# Sheet.net
KiCad netlist of a schematic drawn in Altium Designer
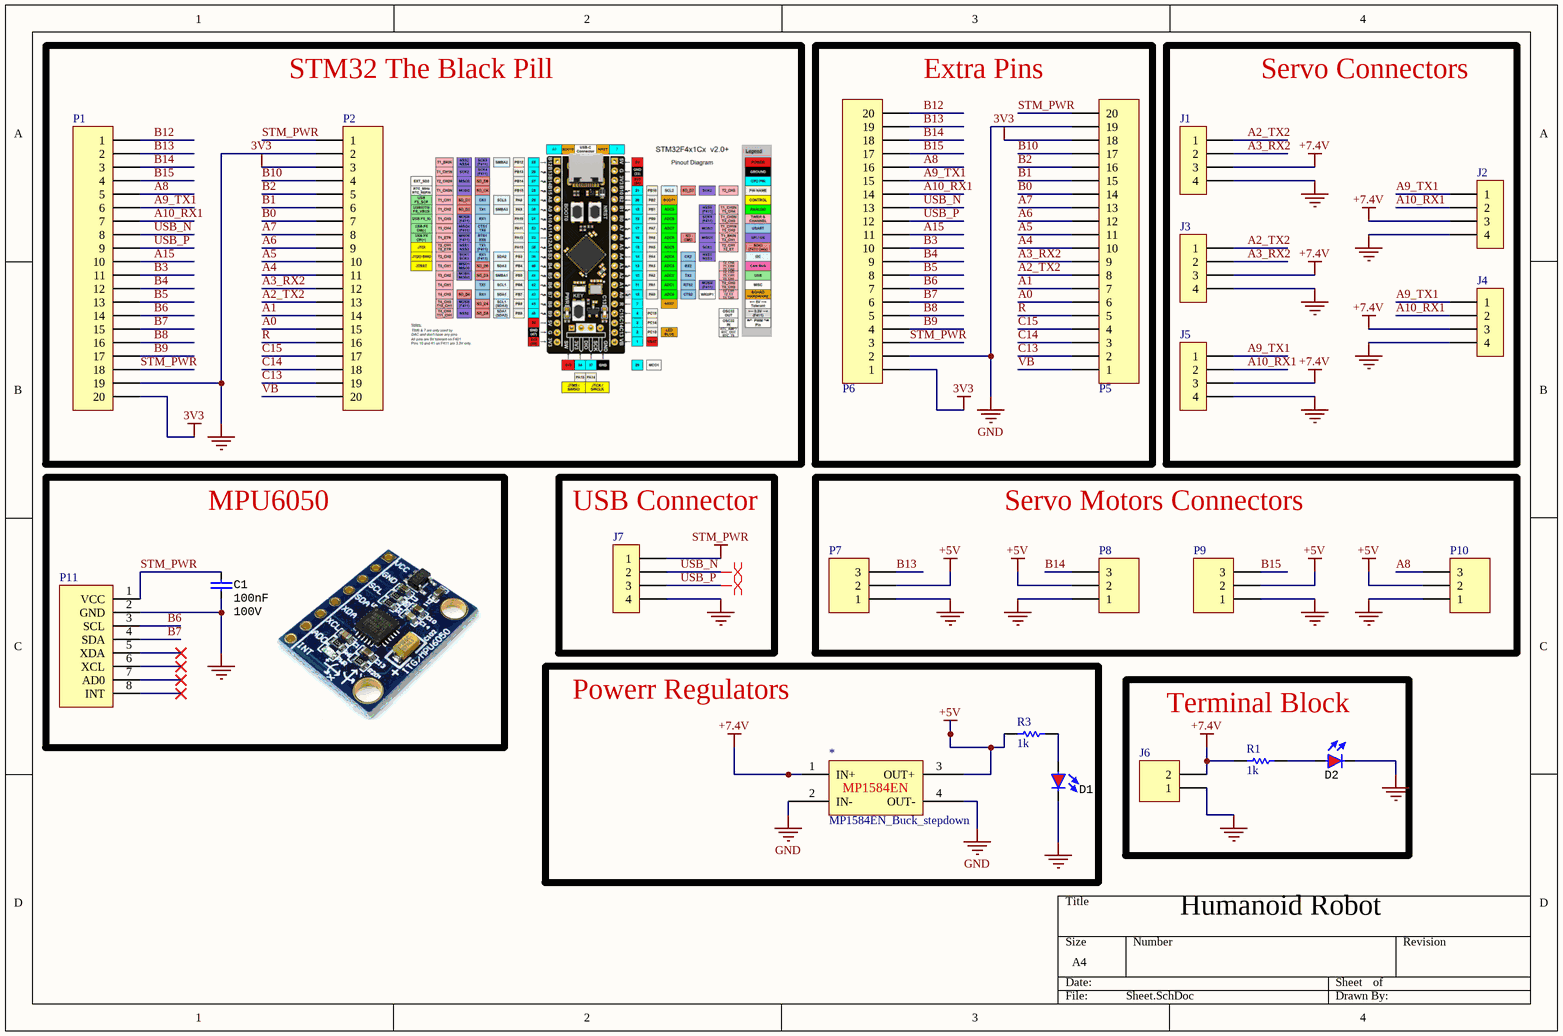
[diagram p0: Sheet.SchDoc]

(export (version "E")
  (design (tool "Eeschema 10.0.6"))
  (components
    (comp (ref "*")
      (value "MP1584EN_Buck_stepdown")
      (footprint "MP1584EN_MODULE")
      (libsource (lib "GradPcb_schlib") (part "MP1584EN_Buck_stepdown"))
    )
    (comp (ref "C1")
      (value "100nF")
      (footprint "CAP Ceramic SMD 0603")
      (description "100V 100nF X7R ±10% 0603 Multilayer Ceramic Capacitors MLCC - SMD/SMT ROHS")
      (fields
        (field (name "MANUFACTURER") "Yageo")
        (field (name "MANUFACTURER PART NUMBER") "CC0603KRX7R0BB104")
        (field (name "VOLTAGE") "100V")
      )
      (libsource (lib "Passive") (part "CAP 0603 100nF 100V X7R 10%"))
    )
    (comp (ref "D1")
      (value "~")
      (footprint "LED SMD 0805R")
      (description "red 0805 Light Emitting Diodes (LED) ROHS")
      (fields
        (field (name "MANUFACTURER") "FOSHAN Nationstar Optoelectronics")
        (field (name "MANUFACTURER PART NUMBER") "NCD0805R1")
      )
      (libsource (lib "diode") (part "LED 0805 Red"))
    )
    (comp (ref "D2")
      (value "~")
      (footprint "LED SMD 0805R")
      (description "red 0805 Light Emitting Diodes (LED) ROHS")
      (fields
        (field (name "MANUFACTURER") "FOSHAN Nationstar Optoelectronics")
        (field (name "MANUFACTURER PART NUMBER") "NCD0805R1")
      )
      (libsource (lib "diode") (part "LED 0805 Red"))
    )
    (comp (ref "J1")
      (value "JST 4")
      (footprint "XH4/2.54mm/180")
      (description "MaleHeader 4x1")
      (libsource (lib "Signal connectors") (part "JST 4"))
    )
    (comp (ref "J2")
      (value "JST 4")
      (footprint "XH4/2.54mm/180")
      (description "MaleHeader 4x1")
      (libsource (lib "") (part "JST 4_1"))
    )
    (comp (ref "J3")
      (value "JST 4")
      (footprint "XH4/2.54mm/180")
      (description "MaleHeader 4x1")
      (libsource (lib "Signal connectors") (part "JST 4"))
    )
    (comp (ref "J4")
      (value "JST 4")
      (footprint "XH4/2.54mm/180")
      (description "MaleHeader 4x1")
      (libsource (lib "") (part "JST 4_1"))
    )
    (comp (ref "J5")
      (value "JST 4")
      (footprint "XH4/2.54mm/180")
      (description "MaleHeader 4x1")
      (libsource (lib "Signal connectors") (part "JST 4"))
    )
    (comp (ref "J6")
      (value "PWR IN")
      (footprint "Connector screw terminal Block TH 1x2 5.0")
      (description "691214110002 - Wire-To-Board Terminal Block, 3.5 mm, 2 Positions, 24 AWG, 16 AWG, 1.5 mm², Screw")
      (fields
        (field (name "MANUFACTURER") "Wurth Electronics")
        (field (name "MANUFACTURER PART NUMBER") "691214110002")
      )
      (libsource (lib "Power connectors") (part "connector screw terminal 1x2"))
    )
    (comp (ref "J7")
      (value "JST 4")
      (footprint "XH4/2.54mm/180")
      (description "MaleHeader 4x1")
      (libsource (lib "Signal connectors") (part "JST 4"))
    )
    (comp (ref "P1")
      (value "Connector Pinheader 1x20")
      (footprint "Header F 2.54X20")
      (description "Header_20x1")
      (libsource (lib "Signal connectors") (part "Connector Pinheader 1x20"))
    )
    (comp (ref "P2")
      (value "Connector Pinheader 1x20")
      (footprint "Header F 2.54X20")
      (description "Header_20x1")
      (libsource (lib "") (part "Connector Pinheader 1x20_1"))
    )
    (comp (ref "P5")
      (value "Connector Pinheader 1x20")
      (footprint "Header F 2.54X20")
      (description "Header_20x1")
      (libsource (lib "") (part "Connector Pinheader 1x20_1"))
    )
    (comp (ref "P6")
      (value "Connector Pinheader 1x20")
      (footprint "Header F 2.54X20")
      (description "Header_20x1")
      (libsource (lib "GradPcb_schlib") (part "Connector Pinheader 1x20"))
    )
    (comp (ref "P7")
      (value "L_gripper")
      (footprint "Header 2.54X3")
      (description "Header_3x1")
      (libsource (lib "") (part "Connector Pinheader 1x3_1"))
    )
    (comp (ref "P8")
      (value "Connector Pinheader 1x3")
      (footprint "Header 2.54X3")
      (description "Header_3x1")
      (libsource (lib "Signal connectors") (part "Connector Pinheader 1x3"))
    )
    (comp (ref "P9")
      (value "R_gripper")
      (footprint "Header 2.54X3")
      (description "Header_3x1")
      (libsource (lib "") (part "Connector Pinheader 1x3_1"))
    )
    (comp (ref "P10")
      (value "Connector Pinheader 1x3")
      (footprint "Header 2.54X3")
      (description "Header_3x1")
      (libsource (lib "Signal connectors") (part "Connector Pinheader 1x3"))
    )
    (comp (ref "P11")
      (value "MPU6050 (GY-521 Module)")
      (footprint "MPU6050 (GY-521 Module)")
      (libsource (lib "Modules") (part "MPU6050 (GY-521 Module)"))
    )
    (comp (ref "R1")
      (value "1k")
      (footprint "RESC2013X70X40ML20T20")
      (description "Chip Resistor, 1 KOhm, +/- 1%, 0.125 W, -55 to 155 degC, 0805 (2013 Metric)")
      (fields (field (name "TOLERANCE") "1%") (field (name "POWER") "125mW"))
      (libsource (lib "Nour's Workspace") (part "RES-2"))
    )
    (comp (ref "R3")
      (value "1k")
      (footprint "RESC2013X70X40ML20T20")
      (description "Chip Resistor, 1 KOhm, +/- 1%, 0.125 W, -55 to 155 degC, 0805 (2013 Metric)")
      (fields (field (name "TOLERANCE") "1%") (field (name "POWER") "125mW"))
      (libsource (lib "Nour's Workspace") (part "RES-2"))
    )
  )
  (nets
    (net (code "1") (name "+5V") (class "Default")
      (node (ref "*") (pin "3") (pinfunction "OUT+_3") (pintype "passive"))
      (node (ref "P10") (pin "2") (pinfunction "2_2") (pintype "passive"))
      (node (ref "P7") (pin "2") (pinfunction "2_2") (pintype "passive"))
      (node (ref "P8") (pin "2") (pinfunction "2_2") (pintype "passive"))
      (node (ref "P9") (pin "2") (pinfunction "2_2") (pintype "passive"))
      (node (ref "R3") (pin "1") (pinfunction "1_1") (pintype "passive"))
    )
    (net (code "2") (name "+7.4V") (class "Default")
      (node (ref "*") (pin "1") (pinfunction "IN+_1") (pintype "passive"))
      (node (ref "J1") (pin "3") (pinfunction "3_3") (pintype "passive"))
      (node (ref "J2") (pin "3") (pinfunction "3_3") (pintype "passive"))
      (node (ref "J3") (pin "3") (pinfunction "3_3") (pintype "passive"))
      (node (ref "J4") (pin "3") (pinfunction "3_3") (pintype "passive"))
      (node (ref "J5") (pin "3") (pinfunction "3_3") (pintype "passive"))
      (node (ref "J6") (pin "2") (pinfunction "2_2") (pintype "passive"))
      (node (ref "R1") (pin "1") (pinfunction "1_1") (pintype "passive"))
    )
    (net (code "3") (name "/A0") (class "Default")
      (node (ref "P2") (pin "15") (pinfunction "15_15") (pintype "passive"))
      (node (ref "P5") (pin "6") (pinfunction "6_6") (pintype "passive"))
    )
    (net (code "4") (name "/A1") (class "Default")
      (node (ref "P2") (pin "14") (pinfunction "14_14") (pintype "passive"))
      (node (ref "P5") (pin "7") (pinfunction "7_7") (pintype "passive"))
    )
    (net (code "5") (name "/A2_TX2") (class "Default")
      (node (ref "J1") (pin "1") (pinfunction "1_1") (pintype "passive"))
      (node (ref "J3") (pin "1") (pinfunction "1_1") (pintype "passive"))
      (node (ref "P2") (pin "13") (pinfunction "13_13") (pintype "passive"))
      (node (ref "P5") (pin "8") (pinfunction "8_8") (pintype "passive"))
    )
    (net (code "6") (name "/A3_RX2") (class "Default")
      (node (ref "J1") (pin "2") (pinfunction "2_2") (pintype "passive"))
      (node (ref "J3") (pin "2") (pinfunction "2_2") (pintype "passive"))
      (node (ref "P2") (pin "12") (pinfunction "12_12") (pintype "passive"))
      (node (ref "P5") (pin "9") (pinfunction "9_9") (pintype "passive"))
    )
    (net (code "7") (name "/A4") (class "Default")
      (node (ref "P2") (pin "11") (pinfunction "11_11") (pintype "passive"))
      (node (ref "P5") (pin "10") (pinfunction "10_10") (pintype "passive"))
    )
    (net (code "8") (name "/A5") (class "Default")
      (node (ref "P2") (pin "10") (pinfunction "10_10") (pintype "passive"))
      (node (ref "P5") (pin "11") (pinfunction "11_11") (pintype "passive"))
    )
    (net (code "9") (name "/A6") (class "Default")
      (node (ref "P2") (pin "9") (pinfunction "9_9") (pintype "passive"))
      (node (ref "P5") (pin "12") (pinfunction "12_12") (pintype "passive"))
    )
    (net (code "10") (name "/A7") (class "Default")
      (node (ref "P2") (pin "8") (pinfunction "8_8") (pintype "passive"))
      (node (ref "P5") (pin "13") (pinfunction "13_13") (pintype "passive"))
    )
    (net (code "11") (name "/A8") (class "Default")
      (node (ref "P1") (pin "5") (pinfunction "5_5") (pintype "passive"))
      (node (ref "P10") (pin "3") (pinfunction "3_3") (pintype "passive"))
      (node (ref "P6") (pin "16") (pinfunction "16_16") (pintype "passive"))
    )
    (net (code "12") (name "/A9_TX1") (class "Default")
      (node (ref "J2") (pin "1") (pinfunction "1_1") (pintype "passive"))
      (node (ref "J4") (pin "1") (pinfunction "1_1") (pintype "passive"))
      (node (ref "J5") (pin "1") (pinfunction "1_1") (pintype "passive"))
      (node (ref "P1") (pin "6") (pinfunction "6_6") (pintype "passive"))
      (node (ref "P6") (pin "15") (pinfunction "15_15") (pintype "passive"))
    )
    (net (code "13") (name "/A10_RX1") (class "Default")
      (node (ref "J2") (pin "2") (pinfunction "2_2") (pintype "passive"))
      (node (ref "J4") (pin "2") (pinfunction "2_2") (pintype "passive"))
      (node (ref "J5") (pin "2") (pinfunction "2_2") (pintype "passive"))
      (node (ref "P1") (pin "7") (pinfunction "7_7") (pintype "passive"))
      (node (ref "P6") (pin "14") (pinfunction "14_14") (pintype "passive"))
    )
    (net (code "14") (name "/A15") (class "Default")
      (node (ref "P1") (pin "10") (pinfunction "10_10") (pintype "passive"))
      (node (ref "P6") (pin "11") (pinfunction "11_11") (pintype "passive"))
    )
    (net (code "15") (name "/B0") (class "Default")
      (node (ref "P2") (pin "7") (pinfunction "7_7") (pintype "passive"))
      (node (ref "P5") (pin "14") (pinfunction "14_14") (pintype "passive"))
    )
    (net (code "16") (name "/B1") (class "Default")
      (node (ref "P2") (pin "6") (pinfunction "6_6") (pintype "passive"))
      (node (ref "P5") (pin "15") (pinfunction "15_15") (pintype "passive"))
    )
    (net (code "17") (name "/B2") (class "Default")
      (node (ref "P2") (pin "5") (pinfunction "5_5") (pintype "passive"))
      (node (ref "P5") (pin "16") (pinfunction "16_16") (pintype "passive"))
    )
    (net (code "18") (name "/B3") (class "Default")
      (node (ref "P1") (pin "11") (pinfunction "11_11") (pintype "passive"))
      (node (ref "P6") (pin "10") (pinfunction "10_10") (pintype "passive"))
    )
    (net (code "19") (name "/B4") (class "Default")
      (node (ref "P1") (pin "12") (pinfunction "12_12") (pintype "passive"))
      (node (ref "P6") (pin "9") (pinfunction "9_9") (pintype "passive"))
    )
    (net (code "20") (name "/B5") (class "Default")
      (node (ref "P1") (pin "13") (pinfunction "13_13") (pintype "passive"))
      (node (ref "P6") (pin "8") (pinfunction "8_8") (pintype "passive"))
    )
    (net (code "21") (name "/B6") (class "Default")
      (node (ref "P1") (pin "14") (pinfunction "14_14") (pintype "passive"))
      (node (ref "P11") (pin "3") (pinfunction "SCL_3") (pintype "passive"))
      (node (ref "P6") (pin "7") (pinfunction "7_7") (pintype "passive"))
    )
    (net (code "22") (name "/B7") (class "Default")
      (node (ref "P1") (pin "15") (pinfunction "15_15") (pintype "passive"))
      (node (ref "P11") (pin "4") (pinfunction "SDA_4") (pintype "passive"))
      (node (ref "P6") (pin "6") (pinfunction "6_6") (pintype "passive"))
    )
    (net (code "23") (name "/B8") (class "Default")
      (node (ref "P1") (pin "16") (pinfunction "16_16") (pintype "passive"))
      (node (ref "P6") (pin "5") (pinfunction "5_5") (pintype "passive"))
    )
    (net (code "24") (name "/B9") (class "Default")
      (node (ref "P1") (pin "17") (pinfunction "17_17") (pintype "passive"))
      (node (ref "P6") (pin "4") (pinfunction "4_4") (pintype "passive"))
    )
    (net (code "25") (name "/B10") (class "Default")
      (node (ref "P2") (pin "4") (pinfunction "4_4") (pintype "passive"))
      (node (ref "P5") (pin "17") (pinfunction "17_17") (pintype "passive"))
    )
    (net (code "26") (name "/B12") (class "Default")
      (node (ref "P1") (pin "1") (pinfunction "1_1") (pintype "passive"))
      (node (ref "P6") (pin "20") (pinfunction "20_20") (pintype "passive"))
    )
    (net (code "27") (name "/B13") (class "Default")
      (node (ref "P1") (pin "2") (pinfunction "2_2") (pintype "passive"))
      (node (ref "P6") (pin "19") (pinfunction "19_19") (pintype "passive"))
      (node (ref "P7") (pin "3") (pinfunction "3_3") (pintype "passive"))
    )
    (net (code "28") (name "/B14") (class "Default")
      (node (ref "P1") (pin "3") (pinfunction "3_3") (pintype "passive"))
      (node (ref "P6") (pin "18") (pinfunction "18_18") (pintype "passive"))
      (node (ref "P8") (pin "3") (pinfunction "3_3") (pintype "passive"))
    )
    (net (code "29") (name "/B15") (class "Default")
      (node (ref "P1") (pin "4") (pinfunction "4_4") (pintype "passive"))
      (node (ref "P6") (pin "17") (pinfunction "17_17") (pintype "passive"))
      (node (ref "P9") (pin "3") (pinfunction "3_3") (pintype "passive"))
    )
    (net (code "30") (name "/C13") (class "Default")
      (node (ref "P2") (pin "19") (pinfunction "19_19") (pintype "passive"))
      (node (ref "P5") (pin "2") (pinfunction "2_2") (pintype "passive"))
    )
    (net (code "31") (name "/C14") (class "Default")
      (node (ref "P2") (pin "18") (pinfunction "18_18") (pintype "passive"))
      (node (ref "P5") (pin "3") (pinfunction "3_3") (pintype "passive"))
    )
    (net (code "32") (name "/C15") (class "Default")
      (node (ref "P2") (pin "17") (pinfunction "17_17") (pintype "passive"))
      (node (ref "P5") (pin "4") (pinfunction "4_4") (pintype "passive"))
    )
    (net (code "33") (name "/R") (class "Default")
      (node (ref "P2") (pin "16") (pinfunction "16_16") (pintype "passive"))
      (node (ref "P5") (pin "5") (pinfunction "5_5") (pintype "passive"))
    )
    (net (code "34") (name "/USB_N") (class "Default")
      (node (ref "J7") (pin "2") (pinfunction "2_2") (pintype "passive"))
      (node (ref "P1") (pin "8") (pinfunction "8_8") (pintype "passive"))
      (node (ref "P6") (pin "13") (pinfunction "13_13") (pintype "passive"))
    )
    (net (code "35") (name "/USB_P") (class "Default")
      (node (ref "J7") (pin "3") (pinfunction "3_3") (pintype "passive"))
      (node (ref "P1") (pin "9") (pinfunction "9_9") (pintype "passive"))
      (node (ref "P6") (pin "12") (pinfunction "12_12") (pintype "passive"))
    )
    (net (code "36") (name "/VB") (class "Default")
      (node (ref "P2") (pin "20") (pinfunction "20_20") (pintype "passive"))
      (node (ref "P5") (pin "1") (pinfunction "1_1") (pintype "passive"))
    )
    (net (code "37") (name "3V3") (class "Default")
      (node (ref "P1") (pin "20") (pinfunction "20_20") (pintype "passive"))
      (node (ref "P2") (pin "3") (pinfunction "3_3") (pintype "passive"))
      (node (ref "P5") (pin "18") (pinfunction "18_18") (pintype "passive"))
      (node (ref "P6") (pin "1") (pinfunction "1_1") (pintype "passive"))
    )
    (net (code "38") (name "GND") (class "Default")
      (node (ref "*") (pin "2") (pinfunction "IN-_2") (pintype "passive"))
      (node (ref "*") (pin "4") (pinfunction "OUT-_4") (pintype "passive"))
      (node (ref "C1") (pin "2") (pinfunction "2_2") (pintype "passive"))
      (node (ref "D1") (pin "2") (pinfunction "2_2") (pintype "passive"))
      (node (ref "D2") (pin "2") (pinfunction "2_2") (pintype "passive"))
      (node (ref "J1") (pin "4") (pinfunction "4_4") (pintype "passive"))
      (node (ref "J2") (pin "4") (pinfunction "4_4") (pintype "passive"))
      (node (ref "J3") (pin "4") (pinfunction "4_4") (pintype "passive"))
      (node (ref "J4") (pin "4") (pinfunction "4_4") (pintype "passive"))
      (node (ref "J5") (pin "4") (pinfunction "4_4") (pintype "passive"))
      (node (ref "J6") (pin "1") (pinfunction "1_1") (pintype "passive"))
      (node (ref "J7") (pin "4") (pinfunction "4_4") (pintype "passive"))
      (node (ref "P1") (pin "19") (pinfunction "19_19") (pintype "passive"))
      (node (ref "P10") (pin "1") (pinfunction "1_1") (pintype "passive"))
      (node (ref "P11") (pin "2") (pinfunction "GND_2") (pintype "passive"))
      (node (ref "P2") (pin "2") (pinfunction "2_2") (pintype "passive"))
      (node (ref "P5") (pin "19") (pinfunction "19_19") (pintype "passive"))
      (node (ref "P6") (pin "2") (pinfunction "2_2") (pintype "passive"))
      (node (ref "P7") (pin "1") (pinfunction "1_1") (pintype "passive"))
      (node (ref "P8") (pin "1") (pinfunction "1_1") (pintype "passive"))
      (node (ref "P9") (pin "1") (pinfunction "1_1") (pintype "passive"))
    )
    (net (code "39") (name "Net-(D1-Pad1)") (class "Default")
      (node (ref "D1") (pin "1") (pinfunction "1_1") (pintype "passive"))
      (node (ref "R3") (pin "2") (pinfunction "2_2") (pintype "passive"))
    )
    (net (code "40") (name "Net-(D2-Pad1)") (class "Default")
      (node (ref "D2") (pin "1") (pinfunction "1_1") (pintype "passive"))
      (node (ref "R1") (pin "2") (pinfunction "2_2") (pintype "passive"))
    )
    (net (code "41") (name "STM_PWR") (class "Default")
      (node (ref "C1") (pin "1") (pinfunction "1_1") (pintype "passive"))
      (node (ref "J7") (pin "1") (pinfunction "1_1") (pintype "passive"))
      (node (ref "P1") (pin "18") (pinfunction "18_18") (pintype "passive"))
      (node (ref "P11") (pin "1") (pinfunction "VCC_1") (pintype "passive"))
      (node (ref "P2") (pin "1") (pinfunction "1_1") (pintype "passive"))
      (node (ref "P5") (pin "20") (pinfunction "20_20") (pintype "passive"))
      (node (ref "P6") (pin "3") (pinfunction "3_3") (pintype "passive"))
    )
    (net (code "42") (name "unconnected-(P11-AD0-Pad7)") (class "Default")
      (node (ref "P11") (pin "7") (pinfunction "AD0_7") (pintype "passive+no_connect"))
    )
    (net (code "43") (name "unconnected-(P11-INT-Pad8)") (class "Default")
      (node (ref "P11") (pin "8") (pinfunction "INT_8") (pintype "passive+no_connect"))
    )
    (net (code "44") (name "unconnected-(P11-XCL-Pad6)") (class "Default")
      (node (ref "P11") (pin "6") (pinfunction "XCL_6") (pintype "passive+no_connect"))
    )
    (net (code "45") (name "unconnected-(P11-XDA-Pad5)") (class "Default")
      (node (ref "P11") (pin "5") (pinfunction "XDA_5") (pintype "passive+no_connect"))
    )
  )
)
